# ProDoc_ChisFlash-MBC5-Plus-v1_21_8M.net
KiCad netlist of a schematic drawn in EasyEDA Pro
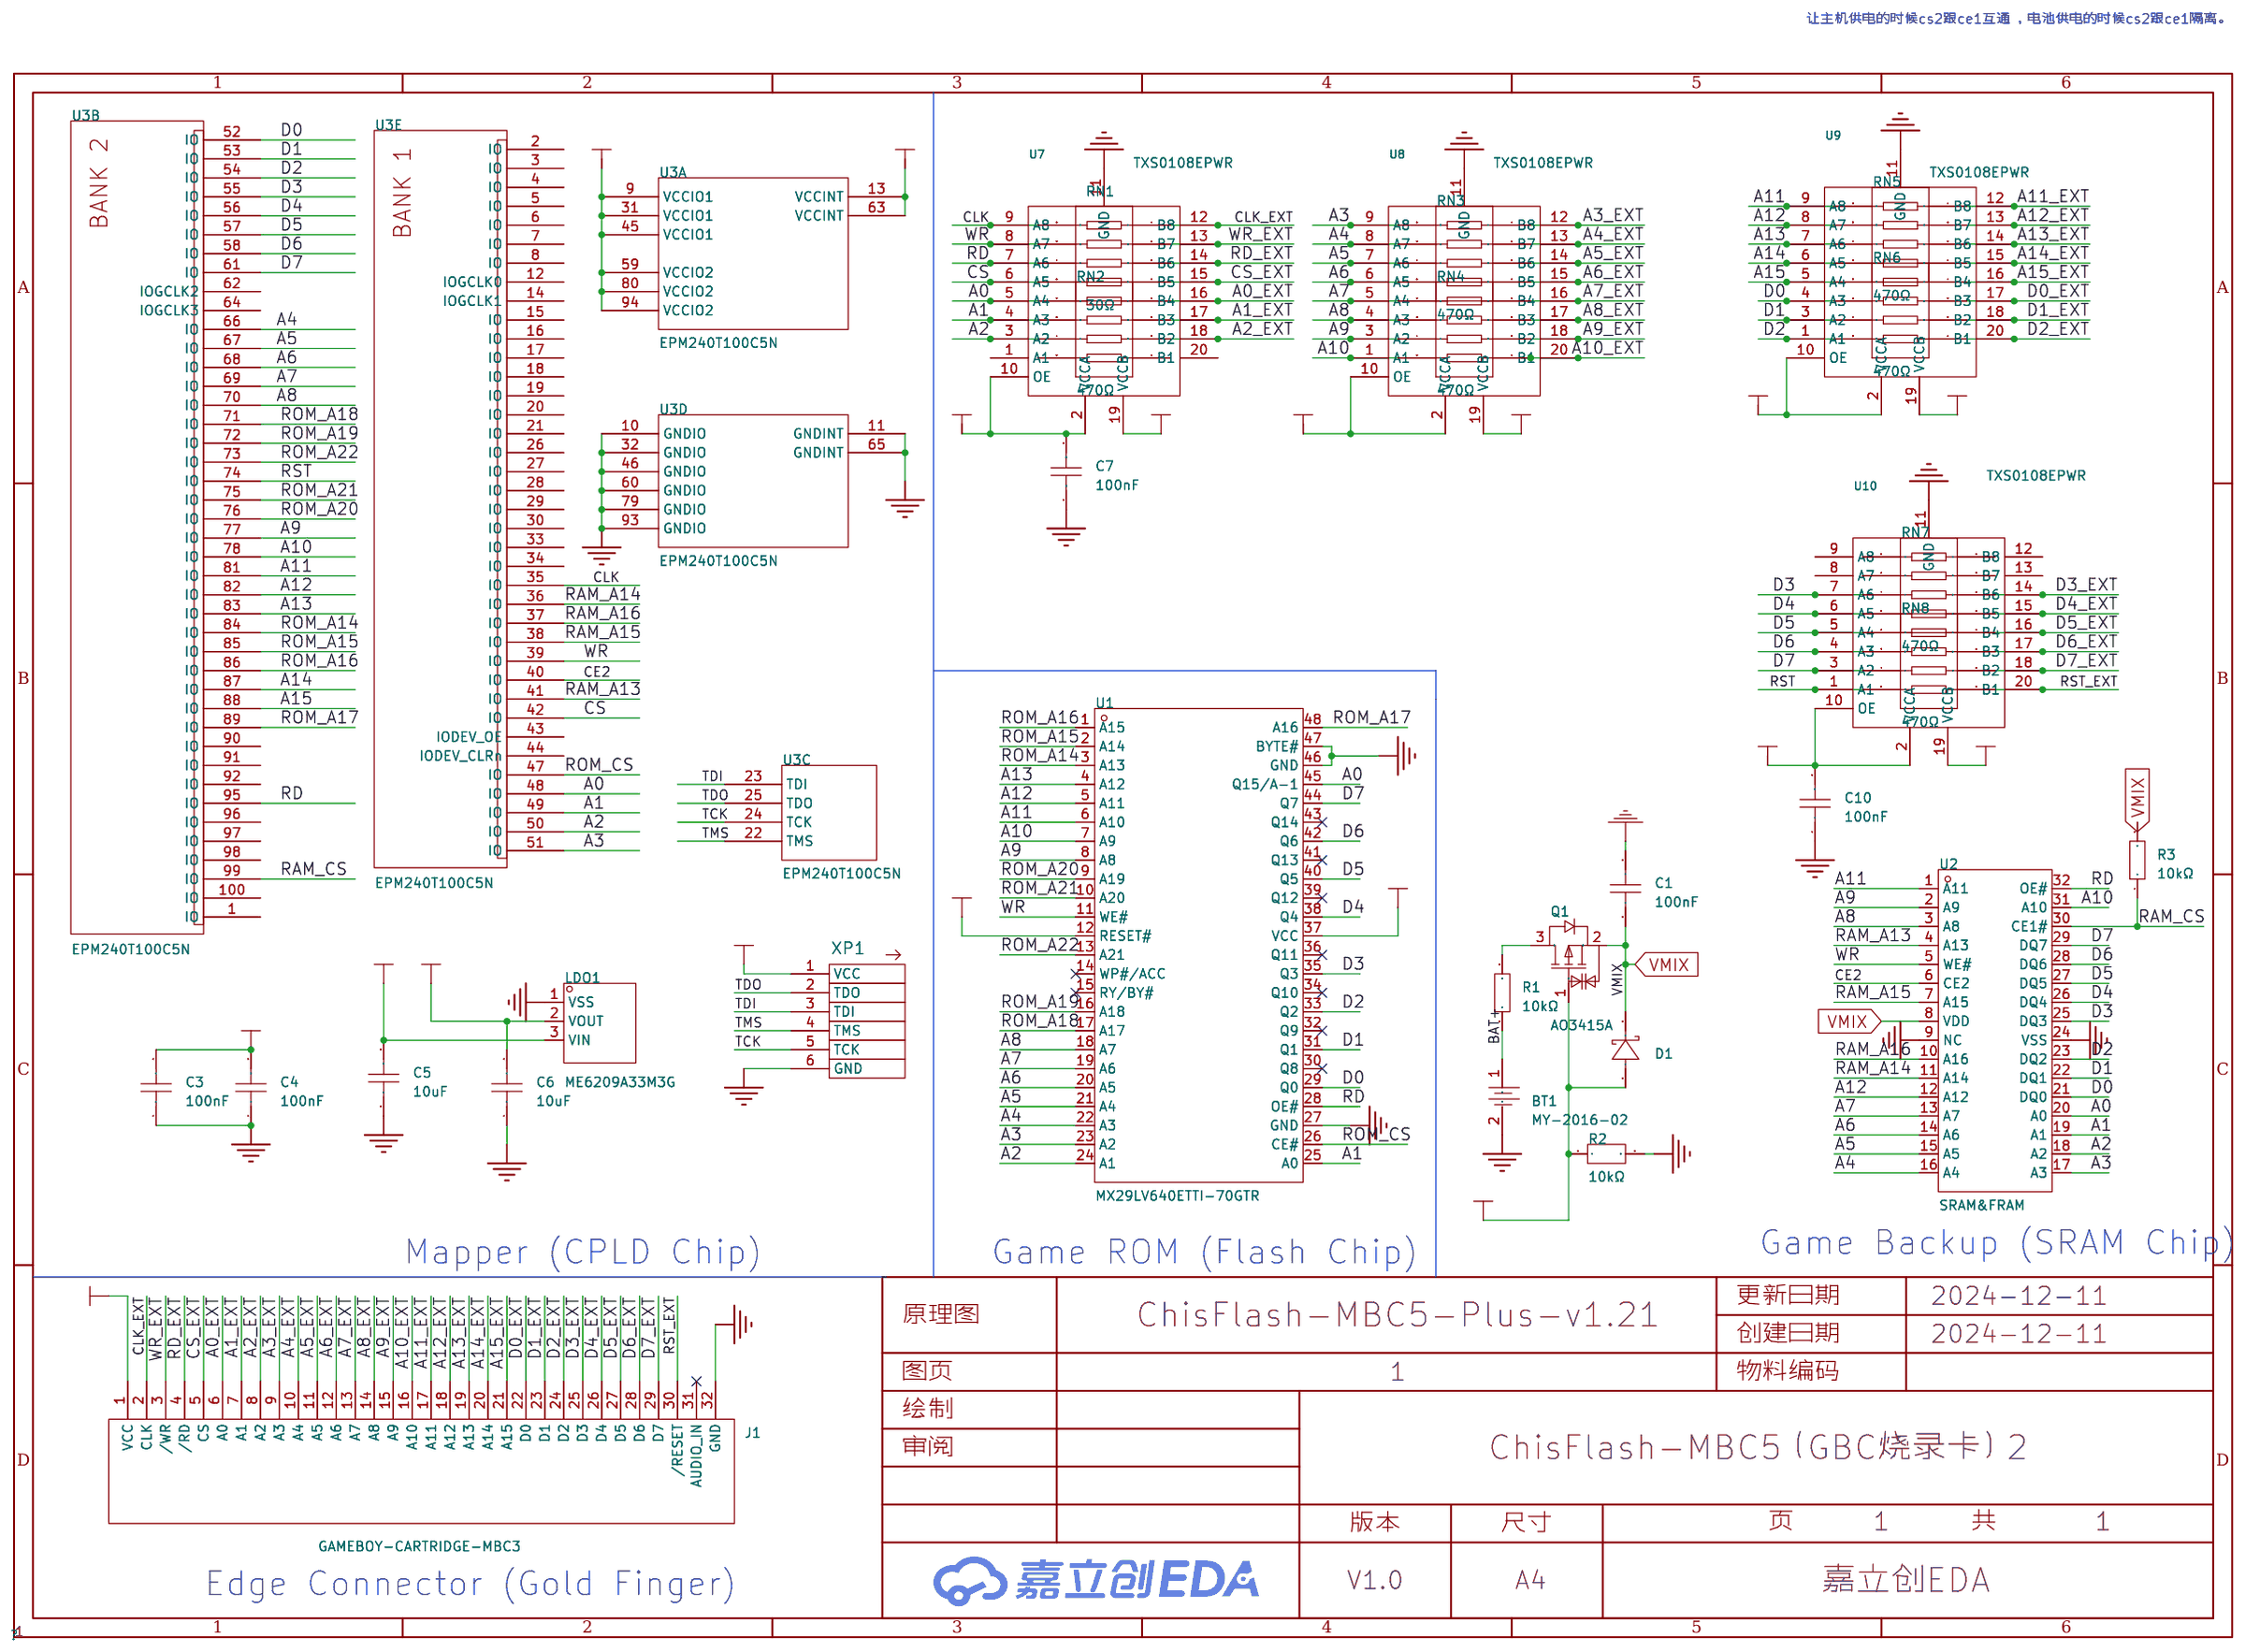
[diagram p0: schematic sheet]

(export (version "E")
  (design (tool "Eeschema 10.0.6"))
  (components
    (comp (ref "BT1")
      (value "MY-2016-02")
      (footprint "easyedapro:BAT-SMD_MY-2032-08")
      (description "连接器类型:电池扣;适用电池规格:CR2016;触头材质:磷青铜;触点电镀:镍;工作温度范围:-25°C~+85°C;")
      (fields (field (name "Manufacturer") "MYOUNG(美阳)"))
      (libsource (lib "easyedapro") (part "MY-2016-02"))
    )
    (comp (ref "C1")
      (value "100nF")
      (footprint "easyedapro:C0603")
      (description "容值:100nF;精度:±10%;额定电压:50V;材质(温度系数):X7R;")
      (fields
        (field (name "Manufacturer Part") "CGA0603X7R104K500JT")
        (field (name "Manufacturer") "HRE(芯声)")
      )
      (libsource (lib "easyedapro") (part "CGA0603X7R104K500JT"))
    )
    (comp (ref "C3")
      (value "100nF")
      (footprint "easyedapro:C0603")
      (description "容值:100nF;精度:±10%;额定电压:50V;材质(温度系数):X7R;")
      (fields
        (field (name "Manufacturer Part") "CGA0603X7R104K500JT")
        (field (name "Manufacturer") "HRE(芯声)")
      )
      (libsource (lib "easyedapro") (part "CGA0603X7R104K500JT"))
    )
    (comp (ref "C4")
      (value "100nF")
      (footprint "easyedapro:C0603")
      (description "容值:100nF;精度:±10%;额定电压:50V;材质(温度系数):X7R;")
      (fields
        (field (name "Manufacturer Part") "CGA0603X7R104K500JT")
        (field (name "Manufacturer") "HRE(芯声)")
      )
      (libsource (lib "easyedapro") (part "CGA0603X7R104K500JT"))
    )
    (comp (ref "C5")
      (value "10uF")
      (footprint "easyedapro:C0603")
      (description "容值:10uF;精度:±20%;额定电压:25V;材质(温度系数):X5R;")
      (fields
        (field (name "Manufacturer Part") "CL10A106MA8NRNC")
        (field (name "Manufacturer") "SAMSUNG(三星)")
      )
      (libsource (lib "easyedapro") (part "CL10A106MA8NRNC"))
    )
    (comp (ref "C6")
      (value "10uF")
      (footprint "easyedapro:C0603")
      (description "容值:10uF;精度:±20%;额定电压:25V;材质(温度系数):X5R;")
      (fields
        (field (name "Manufacturer Part") "CL10A106MA8NRNC")
        (field (name "Manufacturer") "SAMSUNG(三星)")
      )
      (libsource (lib "easyedapro") (part "CL10A106MA8NRNC"))
    )
    (comp (ref "C7")
      (value "100nF")
      (footprint "easyedapro:C0603")
      (description "容值:100nF;精度:±10%;额定电压:50V;材质(温度系数):X7R;")
      (fields
        (field (name "Manufacturer Part") "CGA0603X7R104K500JT")
        (field (name "Manufacturer") "HRE(芯声)")
      )
      (libsource (lib "easyedapro") (part "CGA0603X7R104K500JT"))
    )
    (comp (ref "C10")
      (value "100nF")
      (footprint "easyedapro:C0603")
      (description "容值:100nF;精度:±10%;额定电压:50V;材质(温度系数):X7R;")
      (fields
        (field (name "Manufacturer Part") "CGA0603X7R104K500JT")
        (field (name "Manufacturer") "HRE(芯声)")
      )
      (libsource (lib "easyedapro") (part "CGA0603X7R104K500JT"))
    )
    (comp (ref "D1")
      (value "RB751V-40")
      (footprint "easyedapro:SOD-323_L1.7-W1.3-LS2.6-RD-1")
      (description "二极管配置:独立式;正向压降(Vf):370mV@1mA;直流反向耐压(Vr):40V;平均整流电流(Io):30mA;")
      (fields (field (name "Manufacturer") "宏迦橙"))
      (libsource (lib "easyedapro") (part "RB751V-40_C7502691"))
    )
    (comp (ref "J1")
      (value "GAMEBOY-CARTRIDGE-MBC3")
      (footprint "easyedapro:GAMEBOY_CARTRIDGE_PIN")
      (libsource (lib "easyedapro") (part "GAMEBOY-CARTRIDGE-MBC3"))
    )
    (comp (ref "LDO1")
      (value "ME6209A33M3G")
      (footprint "easyedapro:SOT-23-3_L2.9-W1.6-P1.90-LS2.8-BR")
      (description "输出类型:固定;最大输入电压:18V;输出电压:3.3V;最大输出电流:250mA;电源纹波抑制比(PSRR):-;输出极性:正极;")
      (fields (field (name "Manufacturer") "MICRONE(南京微盟)"))
      (libsource (lib "easyedapro") (part "ME6209A33M3G"))
    )
    (comp (ref "Q1")
      (value "AO3415A")
      (footprint "easyedapro:SOT-23-3_L3.0-W1.7-P0.95-LS2.9-BR")
      (fields (field (name "Manufacturer") "UMW(友台半导体)"))
      (libsource (lib "easyedapro") (part "AO3415A_C347479"))
    )
    (comp (ref "R1")
      (value "10kΩ")
      (footprint "easyedapro:R0603")
      (description "电阻类型:厚膜电阻;阻值:10kΩ;精度:±1%;功率:100mW;温度系数:±100ppm/°C;最大工作电压:75V;工作温度范围:-55°C~+155°C;")
      (fields
        (field (name "Manufacturer Part") "0603WAF1002T5E")
        (field (name "Manufacturer") "UNI-ROYAL(厚声)")
      )
      (libsource (lib "easyedapro") (part "0603WAF1002T5E"))
    )
    (comp (ref "R2")
      (value "10kΩ")
      (footprint "easyedapro:R0603")
      (description "电阻类型:薄膜电阻;阻值:10kΩ;精度:±0.1%;功率:100mW;最大工作电压:75V;温度系数:±25ppm/°C;")
      (fields (field (name "Manufacturer Part") "RT0603BRD1010KL") (field (name "Manufacturer") "YAGEO(国巨)"))
      (libsource (lib "easyedapro") (part "RT0603BRD1010KL"))
    )
    (comp (ref "R3")
      (value "10kΩ")
      (footprint "easyedapro:R0603")
      (description "电阻类型:厚膜电阻;阻值:10kΩ;精度:±1%;功率:100mW;温度系数:±100ppm/°C;最大工作电压:75V;工作温度范围:-55°C~+155°C;")
      (fields
        (field (name "Manufacturer Part") "0603WAF1002T5E")
        (field (name "Manufacturer") "UNI-ROYAL(厚声)")
      )
      (libsource (lib "easyedapro") (part "0603WAF1002T5E"))
    )
    (comp (ref "RN1")
      (value "30Ω")
      (footprint "easyedapro:RES-ARRAY-SMD_0402-8P-L2.0-W1.0-BL")
      (description "电阻器数:4;阻值:30Ω;精度:±5%;单个元件功率:62.5mW;温度系数:±200ppm/°C;")
      (fields (field (name "Manufacturer Part") "RC-MT08W300JT") (field (name "Manufacturer") "FH(风华)"))
      (libsource (lib "easyedapro") (part "RC-MT08W300JT"))
    )
    (comp (ref "RN2")
      (value "470Ω")
      (footprint "easyedapro:RES-ARRAY-SMD_0402-8P-L2.0-W1.0-BL")
      (description "电阻器数:4;阻值:470Ω;精度:±5%;单个元件功率:63mW;温度系数:±200ppm/°C;")
      (fields (field (name "Manufacturer Part") "EXB28V471JX") (field (name "Manufacturer") "PANASONIC(松下)"))
      (libsource (lib "easyedapro") (part "EXB-28V471JX"))
    )
    (comp (ref "RN3")
      (value "470Ω")
      (footprint "easyedapro:RES-ARRAY-SMD_0402-8P-L2.0-W1.0-BL")
      (description "电阻器数:4;阻值:470Ω;精度:±5%;单个元件功率:63mW;温度系数:±200ppm/°C;")
      (fields (field (name "Manufacturer Part") "EXB28V471JX") (field (name "Manufacturer") "PANASONIC(松下)"))
      (libsource (lib "easyedapro") (part "EXB-28V471JX"))
    )
    (comp (ref "RN4")
      (value "470Ω")
      (footprint "easyedapro:RES-ARRAY-SMD_0402-8P-L2.0-W1.0-BL")
      (description "电阻器数:4;阻值:470Ω;精度:±5%;单个元件功率:63mW;温度系数:±200ppm/°C;")
      (fields (field (name "Manufacturer Part") "EXB28V471JX") (field (name "Manufacturer") "PANASONIC(松下)"))
      (libsource (lib "easyedapro") (part "EXB-28V471JX"))
    )
    (comp (ref "RN5")
      (value "470Ω")
      (footprint "easyedapro:RES-ARRAY-SMD_0402-8P-L2.0-W1.0-BL")
      (description "电阻器数:4;阻值:470Ω;精度:±5%;单个元件功率:63mW;温度系数:±200ppm/°C;")
      (fields (field (name "Manufacturer Part") "EXB28V471JX") (field (name "Manufacturer") "PANASONIC(松下)"))
      (libsource (lib "easyedapro") (part "EXB-28V471JX"))
    )
    (comp (ref "RN6")
      (value "470Ω")
      (footprint "easyedapro:RES-ARRAY-SMD_0402-8P-L2.0-W1.0-BL")
      (description "电阻器数:4;阻值:470Ω;精度:±5%;单个元件功率:63mW;温度系数:±200ppm/°C;")
      (fields (field (name "Manufacturer Part") "EXB28V471JX") (field (name "Manufacturer") "PANASONIC(松下)"))
      (libsource (lib "easyedapro") (part "EXB-28V471JX"))
    )
    (comp (ref "RN7")
      (value "470Ω")
      (footprint "easyedapro:RES-ARRAY-SMD_0402-8P-L2.0-W1.0-BL")
      (description "电阻器数:4;阻值:470Ω;精度:±5%;单个元件功率:63mW;温度系数:±200ppm/°C;")
      (fields (field (name "Manufacturer Part") "EXB28V471JX") (field (name "Manufacturer") "PANASONIC(松下)"))
      (libsource (lib "easyedapro") (part "EXB-28V471JX"))
    )
    (comp (ref "RN8")
      (value "470Ω")
      (footprint "easyedapro:RES-ARRAY-SMD_0402-8P-L2.0-W1.0-BL")
      (description "电阻器数:4;阻值:470Ω;精度:±5%;单个元件功率:63mW;温度系数:±200ppm/°C;")
      (fields (field (name "Manufacturer Part") "EXB28V471JX") (field (name "Manufacturer") "PANASONIC(松下)"))
      (libsource (lib "easyedapro") (part "EXB-28V471JX"))
    )
    (comp (ref "U1")
      (value "MX29LV640ETTI-70GTR")
      (footprint "easyedapro:TSOP-48_L12.0-W18.4-P0.50-LS20.0-BL")
      (fields (field (name "Manufacturer") "MXIC(旺宏电子)"))
      (libsource (lib "easyedapro") (part "MX29LV640ETTI-70GTR"))
    )
    (comp (ref "U2")
      (value "SRAM&FRAM")
      (footprint "easyedapro:TSSOP-TSOP二合一")
      (libsource (lib "easyedapro") (part "SRAM&FRAM"))
    )
    (comp (ref "U3")
      (value "EPM240T100C5N")
      (footprint "easyedapro:TQFP-100_L14.0-W14.0-P0.50-LS16.0-BL")
      (description "类型:其它PLD;逻辑门数量:-;逻辑单元数:-;逻辑阵列块数:240;")
      (fields (field (name "Manufacturer") "Intel/Altera"))
      (libsource (lib "easyedapro") (part "EPM240T100C5N"))
    )
    (comp (ref "U7")
      (value "TXS0108EPWR")
      (footprint "easyedapro:TSSOP-20_L6.5-W4.4-P0.65-LS6.4-BL")
      (description "数据速率:60Mbps;电压(VCCA):1.4V~3.6V;电压(VCCB):1.65V~5.5V;电路数:1;每个电路通道数:8;")
      (fields (field (name "Manufacturer") "TI(德州仪器)"))
      (libsource (lib "easyedapro") (part "TXS0108EPWR"))
    )
    (comp (ref "U8")
      (value "TXS0108EPWR")
      (footprint "easyedapro:TSSOP-20_L6.5-W4.4-P0.65-LS6.4-BL")
      (description "数据速率:60Mbps;电压(VCCA):1.4V~3.6V;电压(VCCB):1.65V~5.5V;电路数:1;每个电路通道数:8;")
      (fields (field (name "Manufacturer") "TI(德州仪器)"))
      (libsource (lib "easyedapro") (part "TXS0108EPWR"))
    )
    (comp (ref "U9")
      (value "TXS0108EPWR")
      (footprint "easyedapro:TSSOP-20_L6.5-W4.4-P0.65-LS6.4-BL")
      (description "数据速率:60Mbps;电压(VCCA):1.4V~3.6V;电压(VCCB):1.65V~5.5V;电路数:1;每个电路通道数:8;")
      (fields (field (name "Manufacturer") "TI(德州仪器)"))
      (libsource (lib "easyedapro") (part "TXS0108EPWR"))
    )
    (comp (ref "U10")
      (value "TXS0108EPWR")
      (footprint "easyedapro:TSSOP-20_L6.5-W4.4-P0.65-LS6.4-BL")
      (description "数据速率:60Mbps;电压(VCCA):1.4V~3.6V;电压(VCCB):1.65V~5.5V;电路数:1;每个电路通道数:8;")
      (fields (field (name "Manufacturer") "TI(德州仪器)"))
      (libsource (lib "easyedapro") (part "TXS0108EPWR"))
    )
    (comp (ref "XP1")
      (value "JTAG")
      (footprint "easyedapro:HDR-TH_6P-P1.27-V-M-1")
      (libsource (lib "easyedapro") (part "jtag"))
    )
  )
  (nets
    (net (code "1") (name "+3V3") (class "Default")
      (node (ref "C10") (pin "2") (pinfunction "2_2") (pintype "unspecified"))
      (node (ref "C3") (pin "2") (pinfunction "2_2") (pintype "unspecified"))
      (node (ref "C4") (pin "2") (pinfunction "2_2") (pintype "unspecified"))
      (node (ref "C6") (pin "2") (pinfunction "2_2") (pintype "unspecified"))
      (node (ref "C7") (pin "2") (pinfunction "2_2") (pintype "unspecified"))
      (node (ref "D1") (pin "2") (pinfunction "A_2") (pintype "unspecified"))
      (node (ref "LDO1") (pin "2") (pinfunction "VOUT_2") (pintype "unspecified"))
      (node (ref "Q1") (pin "1") (pinfunction "G_1") (pintype "unspecified"))
      (node (ref "R2") (pin "1") (pinfunction "1_1") (pintype "unspecified"))
      (node (ref "U1") (pin "12") (pinfunction "RESET#_12") (pintype "unspecified"))
      (node (ref "U1") (pin "37") (pinfunction "VCC_37") (pintype "unspecified"))
      (node (ref "U10") (pin "10") (pinfunction "OE_10") (pintype "input"))
      (node (ref "U10") (pin "2") (pinfunction "VCCA_2") (pintype "input"))
      (node (ref "U3") (pin "13") (pinfunction "VCCINT_13") (pintype "unspecified"))
      (node (ref "U3") (pin "31") (pinfunction "VCCIO1_31") (pintype "unspecified"))
      (node (ref "U3") (pin "45") (pinfunction "VCCIO1_45") (pintype "unspecified"))
      (node (ref "U3") (pin "59") (pinfunction "VCCIO2_59") (pintype "unspecified"))
      (node (ref "U3") (pin "63") (pinfunction "VCCINT_63") (pintype "unspecified"))
      (node (ref "U3") (pin "80") (pinfunction "VCCIO2_80") (pintype "unspecified"))
      (node (ref "U3") (pin "9") (pinfunction "VCCIO1_9") (pintype "unspecified"))
      (node (ref "U3") (pin "94") (pinfunction "VCCIO2_94") (pintype "unspecified"))
      (node (ref "U7") (pin "10") (pinfunction "OE_10") (pintype "input"))
      (node (ref "U7") (pin "2") (pinfunction "VCCA_2") (pintype "input"))
      (node (ref "U8") (pin "10") (pinfunction "OE_10") (pintype "input"))
      (node (ref "U8") (pin "2") (pinfunction "VCCA_2") (pintype "input"))
      (node (ref "U9") (pin "10") (pinfunction "OE_10") (pintype "input"))
      (node (ref "U9") (pin "2") (pinfunction "VCCA_2") (pintype "input"))
      (node (ref "XP1") (pin "1") (pinfunction "VCC_1") (pintype "output"))
    )
    (net (code "2") (name "+5V") (class "Default")
      (node (ref "C5") (pin "2") (pinfunction "2_2") (pintype "unspecified"))
      (node (ref "J1") (pin "1") (pinfunction "VCC_1") (pintype "unspecified"))
      (node (ref "LDO1") (pin "3") (pinfunction "VIN_3") (pintype "unspecified"))
      (node (ref "U10") (pin "19") (pinfunction "VCCB_19") (pintype "input"))
      (node (ref "U7") (pin "19") (pinfunction "VCCB_19") (pintype "input"))
      (node (ref "U8") (pin "19") (pinfunction "VCCB_19") (pintype "input"))
      (node (ref "U9") (pin "19") (pinfunction "VCCB_19") (pintype "input"))
    )
    (net (code "3") (name "/A0") (class "Default")
      (node (ref "RN2") (pin "5") (pinfunction "5_5") (pintype "input"))
      (node (ref "U1") (pin "45") (pinfunction "Q15/A-1_45") (pintype "unspecified"))
      (node (ref "U2") (pin "20") (pinfunction "A0_20") (pintype "unspecified"))
      (node (ref "U3") (pin "48") (pinfunction "IO_48") (pintype "bidirectional"))
      (node (ref "U7") (pin "5") (pinfunction "A4_5") (pintype "input"))
    )
    (net (code "4") (name "/A0_EXT") (class "Default")
      (node (ref "J1") (pin "6") (pinfunction "A0_6") (pintype "unspecified"))
      (node (ref "RN2") (pin "4") (pinfunction "4_4") (pintype "input"))
      (node (ref "U7") (pin "16") (pinfunction "B4_16") (pintype "input"))
    )
    (net (code "5") (name "/A1") (class "Default")
      (node (ref "RN2") (pin "6") (pinfunction "6_6") (pintype "input"))
      (node (ref "U1") (pin "25") (pinfunction "A0_25") (pintype "unspecified"))
      (node (ref "U2") (pin "19") (pinfunction "A1_19") (pintype "unspecified"))
      (node (ref "U3") (pin "49") (pinfunction "IO_49") (pintype "bidirectional"))
      (node (ref "U7") (pin "4") (pinfunction "A3_4") (pintype "input"))
    )
    (net (code "6") (name "/A1_EXT") (class "Default")
      (node (ref "J1") (pin "7") (pinfunction "A1_7") (pintype "unspecified"))
      (node (ref "RN2") (pin "3") (pinfunction "3_3") (pintype "input"))
      (node (ref "U7") (pin "17") (pinfunction "B3_17") (pintype "input"))
    )
    (net (code "7") (name "/A2") (class "Default")
      (node (ref "RN2") (pin "7") (pinfunction "7_7") (pintype "input"))
      (node (ref "U1") (pin "24") (pinfunction "A1_24") (pintype "unspecified"))
      (node (ref "U2") (pin "18") (pinfunction "A2_18") (pintype "unspecified"))
      (node (ref "U3") (pin "50") (pinfunction "IO_50") (pintype "bidirectional"))
      (node (ref "U7") (pin "3") (pinfunction "A2_3") (pintype "input"))
    )
    (net (code "8") (name "/A2_EXT") (class "Default")
      (node (ref "J1") (pin "8") (pinfunction "A2_8") (pintype "unspecified"))
      (node (ref "RN2") (pin "2") (pinfunction "2_2") (pintype "input"))
      (node (ref "U7") (pin "18") (pinfunction "B2_18") (pintype "input"))
    )
    (net (code "9") (name "/A3") (class "Default")
      (node (ref "RN3") (pin "5") (pinfunction "5_5") (pintype "input"))
      (node (ref "U1") (pin "23") (pinfunction "A2_23") (pintype "unspecified"))
      (node (ref "U2") (pin "17") (pinfunction "A3_17") (pintype "unspecified"))
      (node (ref "U3") (pin "51") (pinfunction "IO_51") (pintype "bidirectional"))
      (node (ref "U8") (pin "9") (pinfunction "A8_9") (pintype "input"))
    )
    (net (code "10") (name "/A3_EXT") (class "Default")
      (node (ref "J1") (pin "9") (pinfunction "A3_9") (pintype "unspecified"))
      (node (ref "RN3") (pin "4") (pinfunction "4_4") (pintype "input"))
      (node (ref "U8") (pin "12") (pinfunction "B8_12") (pintype "input"))
    )
    (net (code "11") (name "/A4") (class "Default")
      (node (ref "RN3") (pin "6") (pinfunction "6_6") (pintype "input"))
      (node (ref "U1") (pin "22") (pinfunction "A3_22") (pintype "unspecified"))
      (node (ref "U2") (pin "16") (pinfunction "A4_16") (pintype "unspecified"))
      (node (ref "U3") (pin "66") (pinfunction "IO_66") (pintype "bidirectional"))
      (node (ref "U8") (pin "8") (pinfunction "A7_8") (pintype "input"))
    )
    (net (code "12") (name "/A4_EXT") (class "Default")
      (node (ref "J1") (pin "10") (pinfunction "A4_10") (pintype "unspecified"))
      (node (ref "RN3") (pin "3") (pinfunction "3_3") (pintype "input"))
      (node (ref "U8") (pin "13") (pinfunction "B7_13") (pintype "input"))
    )
    (net (code "13") (name "/A5") (class "Default")
      (node (ref "RN3") (pin "7") (pinfunction "7_7") (pintype "input"))
      (node (ref "U1") (pin "21") (pinfunction "A4_21") (pintype "unspecified"))
      (node (ref "U2") (pin "15") (pinfunction "A5_15") (pintype "unspecified"))
      (node (ref "U3") (pin "67") (pinfunction "IO_67") (pintype "bidirectional"))
      (node (ref "U8") (pin "7") (pinfunction "A6_7") (pintype "input"))
    )
    (net (code "14") (name "/A5_EXT") (class "Default")
      (node (ref "J1") (pin "11") (pinfunction "A5_11") (pintype "unspecified"))
      (node (ref "RN3") (pin "2") (pinfunction "2_2") (pintype "input"))
      (node (ref "U8") (pin "14") (pinfunction "B6_14") (pintype "input"))
    )
    (net (code "15") (name "/A6") (class "Default")
      (node (ref "RN3") (pin "8") (pinfunction "8_8") (pintype "input"))
      (node (ref "U1") (pin "20") (pinfunction "A5_20") (pintype "unspecified"))
      (node (ref "U2") (pin "14") (pinfunction "A6_14") (pintype "unspecified"))
      (node (ref "U3") (pin "68") (pinfunction "IO_68") (pintype "bidirectional"))
      (node (ref "U8") (pin "6") (pinfunction "A5_6") (pintype "input"))
    )
    (net (code "16") (name "/A6_EXT") (class "Default")
      (node (ref "J1") (pin "12") (pinfunction "A6_12") (pintype "unspecified"))
      (node (ref "RN3") (pin "1") (pinfunction "1_1") (pintype "input"))
      (node (ref "U8") (pin "15") (pinfunction "B5_15") (pintype "input"))
    )
    (net (code "17") (name "/A7") (class "Default")
      (node (ref "RN4") (pin "5") (pinfunction "5_5") (pintype "input"))
      (node (ref "U1") (pin "19") (pinfunction "A6_19") (pintype "unspecified"))
      (node (ref "U2") (pin "13") (pinfunction "A7_13") (pintype "unspecified"))
      (node (ref "U3") (pin "69") (pinfunction "IO_69") (pintype "bidirectional"))
      (node (ref "U8") (pin "5") (pinfunction "A4_5") (pintype "input"))
    )
    (net (code "18") (name "/A7_EXT") (class "Default")
      (node (ref "J1") (pin "13") (pinfunction "A7_13") (pintype "unspecified"))
      (node (ref "RN4") (pin "4") (pinfunction "4_4") (pintype "input"))
      (node (ref "U8") (pin "16") (pinfunction "B4_16") (pintype "input"))
    )
    (net (code "19") (name "/A8") (class "Default")
      (node (ref "RN4") (pin "6") (pinfunction "6_6") (pintype "input"))
      (node (ref "U1") (pin "18") (pinfunction "A7_18") (pintype "unspecified"))
      (node (ref "U2") (pin "3") (pinfunction "A8_3") (pintype "unspecified"))
      (node (ref "U3") (pin "70") (pinfunction "IO_70") (pintype "bidirectional"))
      (node (ref "U8") (pin "4") (pinfunction "A3_4") (pintype "input"))
    )
    (net (code "20") (name "/A8_EXT") (class "Default")
      (node (ref "J1") (pin "14") (pinfunction "A8_14") (pintype "unspecified"))
      (node (ref "RN4") (pin "3") (pinfunction "3_3") (pintype "input"))
      (node (ref "U8") (pin "17") (pinfunction "B3_17") (pintype "input"))
    )
    (net (code "21") (name "/A9") (class "Default")
      (node (ref "RN4") (pin "7") (pinfunction "7_7") (pintype "input"))
      (node (ref "U1") (pin "8") (pinfunction "A8_8") (pintype "unspecified"))
      (node (ref "U2") (pin "2") (pinfunction "A9_2") (pintype "unspecified"))
      (node (ref "U3") (pin "77") (pinfunction "IO_77") (pintype "bidirectional"))
      (node (ref "U8") (pin "3") (pinfunction "A2_3") (pintype "input"))
    )
    (net (code "22") (name "/A9_EXT") (class "Default")
      (node (ref "J1") (pin "15") (pinfunction "A9_15") (pintype "unspecified"))
      (node (ref "RN4") (pin "2") (pinfunction "2_2") (pintype "input"))
      (node (ref "U8") (pin "18") (pinfunction "B2_18") (pintype "input"))
    )
    (net (code "23") (name "/A10") (class "Default")
      (node (ref "RN4") (pin "8") (pinfunction "8_8") (pintype "input"))
      (node (ref "U1") (pin "7") (pinfunction "A9_7") (pintype "unspecified"))
      (node (ref "U2") (pin "31") (pinfunction "A10_31") (pintype "unspecified"))
      (node (ref "U3") (pin "78") (pinfunction "IO_78") (pintype "bidirectional"))
      (node (ref "U8") (pin "1") (pinfunction "A1_1") (pintype "input"))
    )
    (net (code "24") (name "/A10_EXT") (class "Default")
      (node (ref "J1") (pin "16") (pinfunction "A10_16") (pintype "unspecified"))
      (node (ref "RN4") (pin "1") (pinfunction "1_1") (pintype "input"))
      (node (ref "U8") (pin "20") (pinfunction "B1_20") (pintype "input"))
    )
    (net (code "25") (name "/A11") (class "Default")
      (node (ref "RN5") (pin "5") (pinfunction "5_5") (pintype "input"))
      (node (ref "U1") (pin "6") (pinfunction "A10_6") (pintype "unspecified"))
      (node (ref "U2") (pin "1") (pinfunction "A11_1") (pintype "unspecified"))
      (node (ref "U3") (pin "81") (pinfunction "IO_81") (pintype "bidirectional"))
      (node (ref "U9") (pin "9") (pinfunction "A8_9") (pintype "input"))
    )
    (net (code "26") (name "/A11_EXT") (class "Default")
      (node (ref "J1") (pin "17") (pinfunction "A11_17") (pintype "unspecified"))
      (node (ref "RN5") (pin "4") (pinfunction "4_4") (pintype "input"))
      (node (ref "U9") (pin "12") (pinfunction "B8_12") (pintype "input"))
    )
    (net (code "27") (name "/A12") (class "Default")
      (node (ref "RN5") (pin "6") (pinfunction "6_6") (pintype "input"))
      (node (ref "U1") (pin "5") (pinfunction "A11_5") (pintype "unspecified"))
      (node (ref "U2") (pin "12") (pinfunction "A12_12") (pintype "unspecified"))
      (node (ref "U3") (pin "82") (pinfunction "IO_82") (pintype "bidirectional"))
      (node (ref "U9") (pin "8") (pinfunction "A7_8") (pintype "input"))
    )
    (net (code "28") (name "/A12_EXT") (class "Default")
      (node (ref "J1") (pin "18") (pinfunction "A12_18") (pintype "unspecified"))
      (node (ref "RN5") (pin "3") (pinfunction "3_3") (pintype "input"))
      (node (ref "U9") (pin "13") (pinfunction "B7_13") (pintype "input"))
    )
    (net (code "29") (name "/A13") (class "Default")
      (node (ref "RN5") (pin "7") (pinfunction "7_7") (pintype "input"))
      (node (ref "U1") (pin "4") (pinfunction "A12_4") (pintype "unspecified"))
      (node (ref "U3") (pin "83") (pinfunction "IO_83") (pintype "bidirectional"))
      (node (ref "U9") (pin "7") (pinfunction "A6_7") (pintype "input"))
    )
    (net (code "30") (name "/A13_EXT") (class "Default")
      (node (ref "J1") (pin "19") (pinfunction "A13_19") (pintype "unspecified"))
      (node (ref "RN5") (pin "2") (pinfunction "2_2") (pintype "input"))
      (node (ref "U9") (pin "14") (pinfunction "B6_14") (pintype "input"))
    )
    (net (code "31") (name "/A14") (class "Default")
      (node (ref "RN5") (pin "8") (pinfunction "8_8") (pintype "input"))
      (node (ref "U3") (pin "87") (pinfunction "IO_87") (pintype "bidirectional"))
      (node (ref "U9") (pin "6") (pinfunction "A5_6") (pintype "input"))
    )
    (net (code "32") (name "/A14_EXT") (class "Default")
      (node (ref "J1") (pin "20") (pinfunction "A14_20") (pintype "unspecified"))
      (node (ref "RN5") (pin "1") (pinfunction "1_1") (pintype "input"))
      (node (ref "U9") (pin "15") (pinfunction "B5_15") (pintype "input"))
    )
    (net (code "33") (name "/A15") (class "Default")
      (node (ref "RN6") (pin "5") (pinfunction "5_5") (pintype "input"))
      (node (ref "U3") (pin "88") (pinfunction "IO_88") (pintype "bidirectional"))
      (node (ref "U9") (pin "5") (pinfunction "A4_5") (pintype "input"))
    )
    (net (code "34") (name "/A15_EXT") (class "Default")
      (node (ref "J1") (pin "21") (pinfunction "A15_21") (pintype "unspecified"))
      (node (ref "RN6") (pin "4") (pinfunction "4_4") (pintype "input"))
      (node (ref "U9") (pin "16") (pinfunction "B4_16") (pintype "input"))
    )
    (net (code "35") (name "/BAT+") (class "Default")
      (node (ref "BT1") (pin "1") (pinfunction "1_1") (pintype "input"))
      (node (ref "R1") (pin "1") (pinfunction "1_1") (pintype "input"))
    )
    (net (code "36") (name "/CE2") (class "Default")
      (node (ref "U2") (pin "6") (pinfunction "CE2_6") (pintype "unspecified"))
      (node (ref "U3") (pin "40") (pinfunction "IO_40") (pintype "bidirectional"))
    )
    (net (code "37") (name "/CLK") (class "Default")
      (node (ref "RN1") (pin "5") (pinfunction "5_5") (pintype "input"))
      (node (ref "U3") (pin "35") (pinfunction "IO_35") (pintype "bidirectional"))
      (node (ref "U7") (pin "9") (pinfunction "A8_9") (pintype "input"))
    )
    (net (code "38") (name "/CLK_EXT") (class "Default")
      (node (ref "J1") (pin "2") (pinfunction "CLK_2") (pintype "unspecified"))
      (node (ref "RN1") (pin "4") (pinfunction "4_4") (pintype "input"))
      (node (ref "U7") (pin "12") (pinfunction "B8_12") (pintype "input"))
    )
    (net (code "39") (name "/CS") (class "Default")
      (node (ref "RN1") (pin "8") (pinfunction "8_8") (pintype "input"))
      (node (ref "U3") (pin "42") (pinfunction "IO_42") (pintype "bidirectional"))
      (node (ref "U7") (pin "6") (pinfunction "A5_6") (pintype "input"))
    )
    (net (code "40") (name "/CS_EXT") (class "Default")
      (node (ref "J1") (pin "5") (pinfunction "CS_5") (pintype "unspecified"))
      (node (ref "RN1") (pin "1") (pinfunction "1_1") (pintype "input"))
      (node (ref "U7") (pin "15") (pinfunction "B5_15") (pintype "input"))
    )
    (net (code "41") (name "/D0") (class "Default")
      (node (ref "RN6") (pin "6") (pinfunction "6_6") (pintype "input"))
      (node (ref "U1") (pin "29") (pinfunction "Q0_29") (pintype "unspecified"))
      (node (ref "U2") (pin "21") (pinfunction "DQ0_21") (pintype "unspecified"))
      (node (ref "U3") (pin "52") (pinfunction "IO_52") (pintype "bidirectional"))
      (node (ref "U9") (pin "4") (pinfunction "A3_4") (pintype "input"))
    )
    (net (code "42") (name "/D0_EXT") (class "Default")
      (node (ref "J1") (pin "22") (pinfunction "D0_22") (pintype "unspecified"))
      (node (ref "RN6") (pin "3") (pinfunction "3_3") (pintype "input"))
      (node (ref "U9") (pin "17") (pinfunction "B3_17") (pintype "input"))
    )
    (net (code "43") (name "/D1") (class "Default")
      (node (ref "RN6") (pin "7") (pinfunction "7_7") (pintype "input"))
      (node (ref "U1") (pin "31") (pinfunction "Q1_31") (pintype "unspecified"))
      (node (ref "U2") (pin "22") (pinfunction "DQ1_22") (pintype "unspecified"))
      (node (ref "U3") (pin "53") (pinfunction "IO_53") (pintype "bidirectional"))
      (node (ref "U9") (pin "3") (pinfunction "A2_3") (pintype "input"))
    )
    (net (code "44") (name "/D1_EXT") (class "Default")
      (node (ref "J1") (pin "23") (pinfunction "D1_23") (pintype "unspecified"))
      (node (ref "RN6") (pin "2") (pinfunction "2_2") (pintype "input"))
      (node (ref "U9") (pin "18") (pinfunction "B2_18") (pintype "input"))
    )
    (net (code "45") (name "/D2") (class "Default")
      (node (ref "RN6") (pin "8") (pinfunction "8_8") (pintype "input"))
      (node (ref "U1") (pin "33") (pinfunction "Q2_33") (pintype "unspecified"))
      (node (ref "U2") (pin "23") (pinfunction "DQ2_23") (pintype "unspecified"))
      (node (ref "U3") (pin "54") (pinfunction "IO_54") (pintype "bidirectional"))
      (node (ref "U9") (pin "1") (pinfunction "A1_1") (pintype "input"))
    )
    (net (code "46") (name "/D2_EXT") (class "Default")
      (node (ref "J1") (pin "24") (pinfunction "D2_24") (pintype "unspecified"))
      (node (ref "RN6") (pin "1") (pinfunction "1_1") (pintype "input"))
      (node (ref "U9") (pin "20") (pinfunction "B1_20") (pintype "input"))
    )
    (net (code "47") (name "/D3") (class "Default")
      (node (ref "RN7") (pin "7") (pinfunction "7_7") (pintype "input"))
      (node (ref "U1") (pin "35") (pinfunction "Q3_35") (pintype "unspecified"))
      (node (ref "U10") (pin "7") (pinfunction "A6_7") (pintype "input"))
      (node (ref "U2") (pin "25") (pinfunction "DQ3_25") (pintype "unspecified"))
      (node (ref "U3") (pin "55") (pinfunction "IO_55") (pintype "bidirectional"))
    )
    (net (code "48") (name "/D3_EXT") (class "Default")
      (node (ref "J1") (pin "25") (pinfunction "D3_25") (pintype "unspecified"))
      (node (ref "RN7") (pin "2") (pinfunction "2_2") (pintype "input"))
      (node (ref "U10") (pin "14") (pinfunction "B6_14") (pintype "input"))
    )
    (net (code "49") (name "/D4") (class "Default")
      (node (ref "RN7") (pin "8") (pinfunction "8_8") (pintype "input"))
      (node (ref "U1") (pin "38") (pinfunction "Q4_38") (pintype "unspecified"))
      (node (ref "U10") (pin "6") (pinfunction "A5_6") (pintype "input"))
      (node (ref "U2") (pin "26") (pinfunction "DQ4_26") (pintype "unspecified"))
      (node (ref "U3") (pin "56") (pinfunction "IO_56") (pintype "bidirectional"))
    )
    (net (code "50") (name "/D4_EXT") (class "Default")
      (node (ref "J1") (pin "26") (pinfunction "D4_26") (pintype "unspecified"))
      (node (ref "RN7") (pin "1") (pinfunction "1_1") (pintype "input"))
      (node (ref "U10") (pin "15") (pinfunction "B5_15") (pintype "input"))
    )
    (net (code "51") (name "/D5") (class "Default")
      (node (ref "RN8") (pin "5") (pinfunction "5_5") (pintype "input"))
      (node (ref "U1") (pin "40") (pinfunction "Q5_40") (pintype "unspecified"))
      (node (ref "U10") (pin "5") (pinfunction "A4_5") (pintype "input"))
      (node (ref "U2") (pin "27") (pinfunction "DQ5_27") (pintype "unspecified"))
      (node (ref "U3") (pin "57") (pinfunction "IO_57") (pintype "bidirectional"))
    )
    (net (code "52") (name "/D5_EXT") (class "Default")
      (node (ref "J1") (pin "27") (pinfunction "D5_27") (pintype "unspecified"))
      (node (ref "RN8") (pin "4") (pinfunction "4_4") (pintype "input"))
      (node (ref "U10") (pin "16") (pinfunction "B4_16") (pintype "input"))
    )
    (net (code "53") (name "/D6") (class "Default")
      (node (ref "RN8") (pin "6") (pinfunction "6_6") (pintype "input"))
      (node (ref "U1") (pin "42") (pinfunction "Q6_42") (pintype "unspecified"))
      (node (ref "U10") (pin "4") (pinfunction "A3_4") (pintype "input"))
      (node (ref "U2") (pin "28") (pinfunction "DQ6_28") (pintype "unspecified"))
      (node (ref "U3") (pin "58") (pinfunction "IO_58") (pintype "bidirectional"))
    )
    (net (code "54") (name "/D6_EXT") (class "Default")
      (node (ref "J1") (pin "28") (pinfunction "D6_28") (pintype "unspecified"))
      (node (ref "RN8") (pin "3") (pinfunction "3_3") (pintype "input"))
      (node (ref "U10") (pin "17") (pinfunction "B3_17") (pintype "input"))
    )
    (net (code "55") (name "/D7") (class "Default")
      (node (ref "RN8") (pin "7") (pinfunction "7_7") (pintype "input"))
      (node (ref "U1") (pin "44") (pinfunction "Q7_44") (pintype "unspecified"))
      (node (ref "U10") (pin "3") (pinfunction "A2_3") (pintype "input"))
      (node (ref "U2") (pin "29") (pinfunction "DQ7_29") (pintype "unspecified"))
      (node (ref "U3") (pin "61") (pinfunction "IO_61") (pintype "bidirectional"))
    )
    (net (code "56") (name "/D7_EXT") (class "Default")
      (node (ref "J1") (pin "29") (pinfunction "D7_29") (pintype "unspecified"))
      (node (ref "RN8") (pin "2") (pinfunction "2_2") (pintype "input"))
      (node (ref "U10") (pin "18") (pinfunction "B2_18") (pintype "input"))
    )
    (net (code "57") (name "/RAM_A13") (class "Default")
      (node (ref "U2") (pin "4") (pinfunction "A13_4") (pintype "unspecified"))
      (node (ref "U3") (pin "41") (pinfunction "IO_41") (pintype "bidirectional"))
    )
    (net (code "58") (name "/RAM_A14") (class "Default")
      (node (ref "U2") (pin "11") (pinfunction "A14_11") (pintype "unspecified"))
      (node (ref "U3") (pin "36") (pinfunction "IO_36") (pintype "bidirectional"))
    )
    (net (code "59") (name "/RAM_A15") (class "Default")
      (node (ref "U2") (pin "7") (pinfunction "A15_7") (pintype "unspecified"))
      (node (ref "U3") (pin "38") (pinfunction "IO_38") (pintype "bidirectional"))
    )
    (net (code "60") (name "/RAM_A16") (class "Default")
      (node (ref "U2") (pin "10") (pinfunction "A16_10") (pintype "unspecified"))
      (node (ref "U3") (pin "37") (pinfunction "IO_37") (pintype "bidirectional"))
    )
    (net (code "61") (name "/RAM_CS") (class "Default")
      (node (ref "R3") (pin "1") (pinfunction "1_1") (pintype "input"))
      (node (ref "U2") (pin "30") (pinfunction "CE1#_30") (pintype "unspecified"))
      (node (ref "U3") (pin "99") (pinfunction "IO_99") (pintype "bidirectional"))
    )
    (net (code "62") (name "/RD") (class "Default")
      (node (ref "RN1") (pin "7") (pinfunction "7_7") (pintype "input"))
      (node (ref "U1") (pin "28") (pinfunction "OE#_28") (pintype "unspecified"))
      (node (ref "U2") (pin "32") (pinfunction "OE#_32") (pintype "unspecified"))
      (node (ref "U3") (pin "95") (pinfunction "IO_95") (pintype "bidirectional"))
      (node (ref "U7") (pin "7") (pinfunction "A6_7") (pintype "input"))
    )
    (net (code "63") (name "/RD_EXT") (class "Default")
      (node (ref "J1") (pin "4") (pinfunction "/RD_4") (pintype "unspecified"))
      (node (ref "RN1") (pin "2") (pinfunction "2_2") (pintype "input"))
      (node (ref "U7") (pin "14") (pinfunction "B6_14") (pintype "input"))
    )
    (net (code "64") (name "/ROM_A14") (class "Default")
      (node (ref "U1") (pin "3") (pinfunction "A13_3") (pintype "unspecified"))
      (node (ref "U3") (pin "84") (pinfunction "IO_84") (pintype "bidirectional"))
    )
    (net (code "65") (name "/ROM_A15") (class "Default")
      (node (ref "U1") (pin "2") (pinfunction "A14_2") (pintype "unspecified"))
      (node (ref "U3") (pin "85") (pinfunction "IO_85") (pintype "bidirectional"))
    )
    (net (code "66") (name "/ROM_A16") (class "Default")
      (node (ref "U1") (pin "1") (pinfunction "A15_1") (pintype "unspecified"))
      (node (ref "U3") (pin "86") (pinfunction "IO_86") (pintype "bidirectional"))
    )
    (net (code "67") (name "/ROM_A17") (class "Default")
      (node (ref "U1") (pin "48") (pinfunction "A16_48") (pintype "unspecified"))
      (node (ref "U3") (pin "89") (pinfunction "IO_89") (pintype "bidirectional"))
    )
    (net (code "68") (name "/ROM_A18") (class "Default")
      (node (ref "U1") (pin "17") (pinfunction "A17_17") (pintype "unspecified"))
      (node (ref "U3") (pin "71") (pinfunction "IO_71") (pintype "bidirectional"))
    )
    (net (code "69") (name "/ROM_A19") (class "Default")
      (node (ref "U1") (pin "16") (pinfunction "A18_16") (pintype "unspecified"))
      (node (ref "U3") (pin "72") (pinfunction "IO_72") (pintype "bidirectional"))
    )
    (net (code "70") (name "/ROM_A20") (class "Default")
      (node (ref "U1") (pin "9") (pinfunction "A19_9") (pintype "unspecified"))
      (node (ref "U3") (pin "76") (pinfunction "IO_76") (pintype "bidirectional"))
    )
    (net (code "71") (name "/ROM_A21") (class "Default")
      (node (ref "U1") (pin "10") (pinfunction "A20_10") (pintype "unspecified"))
      (node (ref "U3") (pin "75") (pinfunction "IO_75") (pintype "bidirectional"))
    )
    (net (code "72") (name "/ROM_A22") (class "Default")
      (node (ref "U1") (pin "13") (pinfunction "A21_13") (pintype "unspecified"))
      (node (ref "U3") (pin "73") (pinfunction "IO_73") (pintype "bidirectional"))
    )
    (net (code "73") (name "/ROM_CS") (class "Default")
      (node (ref "U1") (pin "26") (pinfunction "CE#_26") (pintype "unspecified"))
      (node (ref "U3") (pin "47") (pinfunction "IO_47") (pintype "bidirectional"))
    )
    (net (code "74") (name "/RST") (class "Default")
      (node (ref "RN8") (pin "8") (pinfunction "8_8") (pintype "input"))
      (node (ref "U10") (pin "1") (pinfunction "A1_1") (pintype "input"))
      (node (ref "U3") (pin "74") (pinfunction "IO_74") (pintype "bidirectional"))
    )
    (net (code "75") (name "/RST_EXT") (class "Default")
      (node (ref "J1") (pin "30") (pinfunction "/RESET_30") (pintype "unspecified"))
      (node (ref "RN8") (pin "1") (pinfunction "1_1") (pintype "input"))
      (node (ref "U10") (pin "20") (pinfunction "B1_20") (pintype "input"))
    )
    (net (code "76") (name "/TCK") (class "Default")
      (node (ref "U3") (pin "24") (pinfunction "TCK_24") (pintype "unspecified"))
      (node (ref "XP1") (pin "5") (pinfunction "TCK_5") (pintype "input"))
    )
    (net (code "77") (name "/TDI") (class "Default")
      (node (ref "U3") (pin "23") (pinfunction "TDI_23") (pintype "unspecified"))
      (node (ref "XP1") (pin "3") (pinfunction "TDI_3") (pintype "output"))
    )
    (net (code "78") (name "/TDO") (class "Default")
      (node (ref "U3") (pin "25") (pinfunction "TDO_25") (pintype "output"))
      (node (ref "XP1") (pin "2") (pinfunction "TDO_2") (pintype "output"))
    )
    (net (code "79") (name "/TMS") (class "Default")
      (node (ref "U3") (pin "22") (pinfunction "TMS_22") (pintype "unspecified"))
      (node (ref "XP1") (pin "4") (pinfunction "TMS_4") (pintype "output"))
    )
    (net (code "80") (name "/WR") (class "Default")
      (node (ref "RN1") (pin "6") (pinfunction "6_6") (pintype "input"))
      (node (ref "U1") (pin "11") (pinfunction "WE#_11") (pintype "unspecified"))
      (node (ref "U2") (pin "5") (pinfunction "WE#_5") (pintype "unspecified"))
      (node (ref "U3") (pin "39") (pinfunction "IO_39") (pintype "bidirectional"))
      (node (ref "U7") (pin "8") (pinfunction "A7_8") (pintype "input"))
    )
    (net (code "81") (name "/WR_EXT") (class "Default")
      (node (ref "J1") (pin "3") (pinfunction "/WR_3") (pintype "unspecified"))
      (node (ref "RN1") (pin "3") (pinfunction "3_3") (pintype "input"))
      (node (ref "U7") (pin "13") (pinfunction "B7_13") (pintype "input"))
    )
    (net (code "82") (name "GND") (class "Default")
      (node (ref "BT1") (pin "2") (pinfunction "2_2") (pintype "input"))
      (node (ref "C1") (pin "1") (pinfunction "1_1") (pintype "unspecified"))
      (node (ref "C10") (pin "1") (pinfunction "1_1") (pintype "unspecified"))
      (node (ref "C3") (pin "1") (pinfunction "1_1") (pintype "unspecified"))
      (node (ref "C4") (pin "1") (pinfunction "1_1") (pintype "unspecified"))
      (node (ref "C5") (pin "1") (pinfunction "1_1") (pintype "unspecified"))
      (node (ref "C6") (pin "1") (pinfunction "1_1") (pintype "unspecified"))
      (node (ref "C7") (pin "1") (pinfunction "1_1") (pintype "unspecified"))
      (node (ref "J1") (pin "32") (pinfunction "GND_32") (pintype "unspecified"))
      (node (ref "LDO1") (pin "1") (pinfunction "VSS_1") (pintype "unspecified"))
      (node (ref "R2") (pin "2") (pinfunction "2_2") (pintype "unspecified"))
      (node (ref "U1") (pin "27") (pinfunction "GND_27") (pintype "unspecified"))
      (node (ref "U1") (pin "46") (pinfunction "GND_46") (pintype "unspecified"))
      (node (ref "U1") (pin "47") (pinfunction "BYTE#_47") (pintype "unspecified"))
      (node (ref "U10") (pin "11") (pinfunction "GND_11") (pintype "input"))
      (node (ref "U2") (pin "24") (pinfunction "VSS_24") (pintype "unspecified"))
      (node (ref "U2") (pin "9") (pinfunction "NC_9") (pintype "unspecified"))
      (node (ref "U3") (pin "10") (pinfunction "GNDIO_10") (pintype "unspecified"))
      (node (ref "U3") (pin "11") (pinfunction "GNDINT_11") (pintype "unspecified"))
      (node (ref "U3") (pin "32") (pinfunction "GNDIO_32") (pintype "unspecified"))
      (node (ref "U3") (pin "46") (pinfunction "GNDIO_46") (pintype "unspecified"))
      (node (ref "U3") (pin "60") (pinfunction "GNDIO_60") (pintype "unspecified"))
      (node (ref "U3") (pin "65") (pinfunction "GNDINT_65") (pintype "unspecified"))
      (node (ref "U3") (pin "79") (pinfunction "GNDIO_79") (pintype "unspecified"))
      (node (ref "U3") (pin "93") (pinfunction "GNDIO_93") (pintype "unspecified"))
      (node (ref "U7") (pin "11") (pinfunction "GND_11") (pintype "input"))
      (node (ref "U8") (pin "11") (pinfunction "GND_11") (pintype "input"))
      (node (ref "U9") (pin "11") (pinfunction "GND_11") (pintype "input"))
      (node (ref "XP1") (pin "6") (pinfunction "GND_6") (pintype "input"))
    )
    (net (code "83") (name "Net-(Q1-D)") (class "Default")
      (node (ref "Q1") (pin "3") (pinfunction "D_3") (pintype "unspecified"))
      (node (ref "R1") (pin "2") (pinfunction "2_2") (pintype "input"))
    )
    (net (code "84") (name "VMIX") (class "Default")
      (node (ref "C1") (pin "2") (pinfunction "2_2") (pintype "unspecified"))
      (node (ref "D1") (pin "1") (pinfunction "K_1") (pintype "unspecified"))
      (node (ref "Q1") (pin "2") (pinfunction "S_2") (pintype "unspecified"))
      (node (ref "R3") (pin "2") (pinfunction "2_2") (pintype "input"))
      (node (ref "U2") (pin "8") (pinfunction "VDD_8") (pintype "unspecified"))
    )
    (net (code "85") (name "unconnected-(J1-AUDIO_IN-Pad31)") (class "Default")
      (node (ref "J1") (pin "31") (pinfunction "AUDIO_IN_31") (pintype "unspecified+no_connect"))
    )
    (net (code "86") (name "unconnected-(RN2-Pad1)") (class "Default")
      (node (ref "RN2") (pin "1") (pinfunction "1_1") (pintype "input"))
    )
    (net (code "87") (name "unconnected-(RN2-Pad8)") (class "Default")
      (node (ref "RN2") (pin "8") (pinfunction "8_8") (pintype "input"))
    )
    (net (code "88") (name "unconnected-(RN7-Pad3)") (class "Default")
      (node (ref "RN7") (pin "3") (pinfunction "3_3") (pintype "input"))
    )
    (net (code "89") (name "unconnected-(RN7-Pad4)") (class "Default")
      (node (ref "RN7") (pin "4") (pinfunction "4_4") (pintype "input"))
    )
    (net (code "90") (name "unconnected-(RN7-Pad5)") (class "Default")
      (node (ref "RN7") (pin "5") (pinfunction "5_5") (pintype "input"))
    )
    (net (code "91") (name "unconnected-(RN7-Pad6)") (class "Default")
      (node (ref "RN7") (pin "6") (pinfunction "6_6") (pintype "input"))
    )
    (net (code "92") (name "unconnected-(U1-Q8-Pad30)") (class "Default")
      (node (ref "U1") (pin "30") (pinfunction "Q8_30") (pintype "unspecified+no_connect"))
    )
    (net (code "93") (name "unconnected-(U1-Q9-Pad32)") (class "Default")
      (node (ref "U1") (pin "32") (pinfunction "Q9_32") (pintype "unspecified+no_connect"))
    )
    (net (code "94") (name "unconnected-(U1-Q10-Pad34)") (class "Default")
      (node (ref "U1") (pin "34") (pinfunction "Q10_34") (pintype "unspecified+no_connect"))
    )
    (net (code "95") (name "unconnected-(U1-Q11-Pad36)") (class "Default")
      (node (ref "U1") (pin "36") (pinfunction "Q11_36") (pintype "unspecified+no_connect"))
    )
    (net (code "96") (name "unconnected-(U1-Q12-Pad39)") (class "Default")
      (node (ref "U1") (pin "39") (pinfunction "Q12_39") (pintype "unspecified+no_connect"))
    )
    (net (code "97") (name "unconnected-(U1-Q13-Pad41)") (class "Default")
      (node (ref "U1") (pin "41") (pinfunction "Q13_41") (pintype "unspecified+no_connect"))
    )
    (net (code "98") (name "unconnected-(U1-Q14-Pad43)") (class "Default")
      (node (ref "U1") (pin "43") (pinfunction "Q14_43") (pintype "unspecified+no_connect"))
    )
    (net (code "99") (name "unconnected-(U1-RY{slash}BY#-Pad15)") (class "Default")
      (node (ref "U1") (pin "15") (pinfunction "RY/BY#_15") (pintype "unspecified+no_connect"))
    )
    (net (code "100") (name "unconnected-(U1-WP#{slash}ACC-Pad14)") (class "Default")
      (node (ref "U1") (pin "14") (pinfunction "WP#/ACC_14") (pintype "unspecified+no_connect"))
    )
    (net (code "101") (name "unconnected-(U3B-IO-Pad1)") (class "Default")
      (node (ref "U3") (pin "1") (pinfunction "IO_1") (pintype "bidirectional"))
    )
    (net (code "102") (name "unconnected-(U3B-IO-Pad90)") (class "Default")
      (node (ref "U3") (pin "90") (pinfunction "IO_90") (pintype "bidirectional"))
    )
    (net (code "103") (name "unconnected-(U3B-IO-Pad91)") (class "Default")
      (node (ref "U3") (pin "91") (pinfunction "IO_91") (pintype "bidirectional"))
    )
    (net (code "104") (name "unconnected-(U3B-IO-Pad92)") (class "Default")
      (node (ref "U3") (pin "92") (pinfunction "IO_92") (pintype "bidirectional"))
    )
    (net (code "105") (name "unconnected-(U3B-IO-Pad96)") (class "Default")
      (node (ref "U3") (pin "96") (pinfunction "IO_96") (pintype "bidirectional"))
    )
    (net (code "106") (name "unconnected-(U3B-IO-Pad97)") (class "Default")
      (node (ref "U3") (pin "97") (pinfunction "IO_97") (pintype "bidirectional"))
    )
    (net (code "107") (name "unconnected-(U3B-IO-Pad98)") (class "Default")
      (node (ref "U3") (pin "98") (pinfunction "IO_98") (pintype "bidirectional"))
    )
    (net (code "108") (name "unconnected-(U3B-IO-Pad100)") (class "Default")
      (node (ref "U3") (pin "100") (pinfunction "IO_100") (pintype "bidirectional"))
    )
    (net (code "109") (name "unconnected-(U3B-IOGCLK2-Pad62)") (class "Default")
      (node (ref "U3") (pin "62") (pinfunction "IOGCLK2_62") (pintype "bidirectional"))
    )
    (net (code "110") (name "unconnected-(U3B-IOGCLK3-Pad64)") (class "Default")
      (node (ref "U3") (pin "64") (pinfunction "IOGCLK3_64") (pintype "bidirectional"))
    )
    (net (code "111") (name "unconnected-(U3E-IO-Pad2)") (class "Default")
      (node (ref "U3") (pin "2") (pinfunction "IO_2") (pintype "bidirectional"))
    )
    (net (code "112") (name "unconnected-(U3E-IO-Pad3)") (class "Default")
      (node (ref "U3") (pin "3") (pinfunction "IO_3") (pintype "bidirectional"))
    )
    (net (code "113") (name "unconnected-(U3E-IO-Pad4)") (class "Default")
      (node (ref "U3") (pin "4") (pinfunction "IO_4") (pintype "bidirectional"))
    )
    (net (code "114") (name "unconnected-(U3E-IO-Pad5)") (class "Default")
      (node (ref "U3") (pin "5") (pinfunction "IO_5") (pintype "bidirectional"))
    )
    (net (code "115") (name "unconnected-(U3E-IO-Pad6)") (class "Default")
      (node (ref "U3") (pin "6") (pinfunction "IO_6") (pintype "bidirectional"))
    )
    (net (code "116") (name "unconnected-(U3E-IO-Pad7)") (class "Default")
      (node (ref "U3") (pin "7") (pinfunction "IO_7") (pintype "bidirectional"))
    )
    (net (code "117") (name "unconnected-(U3E-IO-Pad8)") (class "Default")
      (node (ref "U3") (pin "8") (pinfunction "IO_8") (pintype "bidirectional"))
    )
    (net (code "118") (name "unconnected-(U3E-IO-Pad15)") (class "Default")
      (node (ref "U3") (pin "15") (pinfunction "IO_15") (pintype "bidirectional"))
    )
    (net (code "119") (name "unconnected-(U3E-IO-Pad16)") (class "Default")
      (node (ref "U3") (pin "16") (pinfunction "IO_16") (pintype "bidirectional"))
    )
    (net (code "120") (name "unconnected-(U3E-IO-Pad17)") (class "Default")
      (node (ref "U3") (pin "17") (pinfunction "IO_17") (pintype "bidirectional"))
    )
    (net (code "121") (name "unconnected-(U3E-IO-Pad18)") (class "Default")
      (node (ref "U3") (pin "18") (pinfunction "IO_18") (pintype "bidirectional"))
    )
    (net (code "122") (name "unconnected-(U3E-IO-Pad19)") (class "Default")
      (node (ref "U3") (pin "19") (pinfunction "IO_19") (pintype "bidirectional"))
    )
    (net (code "123") (name "unconnected-(U3E-IO-Pad20)") (class "Default")
      (node (ref "U3") (pin "20") (pinfunction "IO_20") (pintype "bidirectional"))
    )
    (net (code "124") (name "unconnected-(U3E-IO-Pad21)") (class "Default")
      (node (ref "U3") (pin "21") (pinfunction "IO_21") (pintype "bidirectional"))
    )
    (net (code "125") (name "unconnected-(U3E-IO-Pad26)") (class "Default")
      (node (ref "U3") (pin "26") (pinfunction "IO_26") (pintype "bidirectional"))
    )
    (net (code "126") (name "unconnected-(U3E-IO-Pad27)") (class "Default")
      (node (ref "U3") (pin "27") (pinfunction "IO_27") (pintype "bidirectional"))
    )
    (net (code "127") (name "unconnected-(U3E-IO-Pad28)") (class "Default")
      (node (ref "U3") (pin "28") (pinfunction "IO_28") (pintype "bidirectional"))
    )
    (net (code "128") (name "unconnected-(U3E-IO-Pad29)") (class "Default")
      (node (ref "U3") (pin "29") (pinfunction "IO_29") (pintype "bidirectional"))
    )
    (net (code "129") (name "unconnected-(U3E-IO-Pad30)") (class "Default")
      (node (ref "U3") (pin "30") (pinfunction "IO_30") (pintype "bidirectional"))
    )
    (net (code "130") (name "unconnected-(U3E-IO-Pad33)") (class "Default")
      (node (ref "U3") (pin "33") (pinfunction "IO_33") (pintype "bidirectional"))
    )
    (net (code "131") (name "unconnected-(U3E-IO-Pad34)") (class "Default")
      (node (ref "U3") (pin "34") (pinfunction "IO_34") (pintype "bidirectional"))
    )
    (net (code "132") (name "unconnected-(U3E-IODEV_CLRn-Pad44)") (class "Default")
      (node (ref "U3") (pin "44") (pinfunction "IODEV_CLRn_44") (pintype "bidirectional"))
    )
    (net (code "133") (name "unconnected-(U3E-IODEV_OE-Pad43)") (class "Default")
      (node (ref "U3") (pin "43") (pinfunction "IODEV_OE_43") (pintype "bidirectional"))
    )
    (net (code "134") (name "unconnected-(U3E-IOGCLK0-Pad12)") (class "Default")
      (node (ref "U3") (pin "12") (pinfunction "IOGCLK0_12") (pintype "bidirectional"))
    )
    (net (code "135") (name "unconnected-(U3E-IOGCLK1-Pad14)") (class "Default")
      (node (ref "U3") (pin "14") (pinfunction "IOGCLK1_14") (pintype "bidirectional"))
    )
    (net (code "136") (name "unconnected-(U7-A1-Pad1)") (class "Default")
      (node (ref "U7") (pin "1") (pinfunction "A1_1") (pintype "input"))
    )
    (net (code "137") (name "unconnected-(U7-B1-Pad20)") (class "Default")
      (node (ref "U7") (pin "20") (pinfunction "B1_20") (pintype "input"))
    )
    (net (code "138") (name "unconnected-(U10-A7-Pad8)") (class "Default")
      (node (ref "U10") (pin "8") (pinfunction "A7_8") (pintype "input"))
    )
    (net (code "139") (name "unconnected-(U10-A8-Pad9)") (class "Default")
      (node (ref "U10") (pin "9") (pinfunction "A8_9") (pintype "input"))
    )
    (net (code "140") (name "unconnected-(U10-B7-Pad13)") (class "Default")
      (node (ref "U10") (pin "13") (pinfunction "B7_13") (pintype "input"))
    )
    (net (code "141") (name "unconnected-(U10-B8-Pad12)") (class "Default")
      (node (ref "U10") (pin "12") (pinfunction "B8_12") (pintype "input"))
    )
  )
)
